# goduino3-v0_22.net
KiCad netlist of a schematic drawn in EAGLE
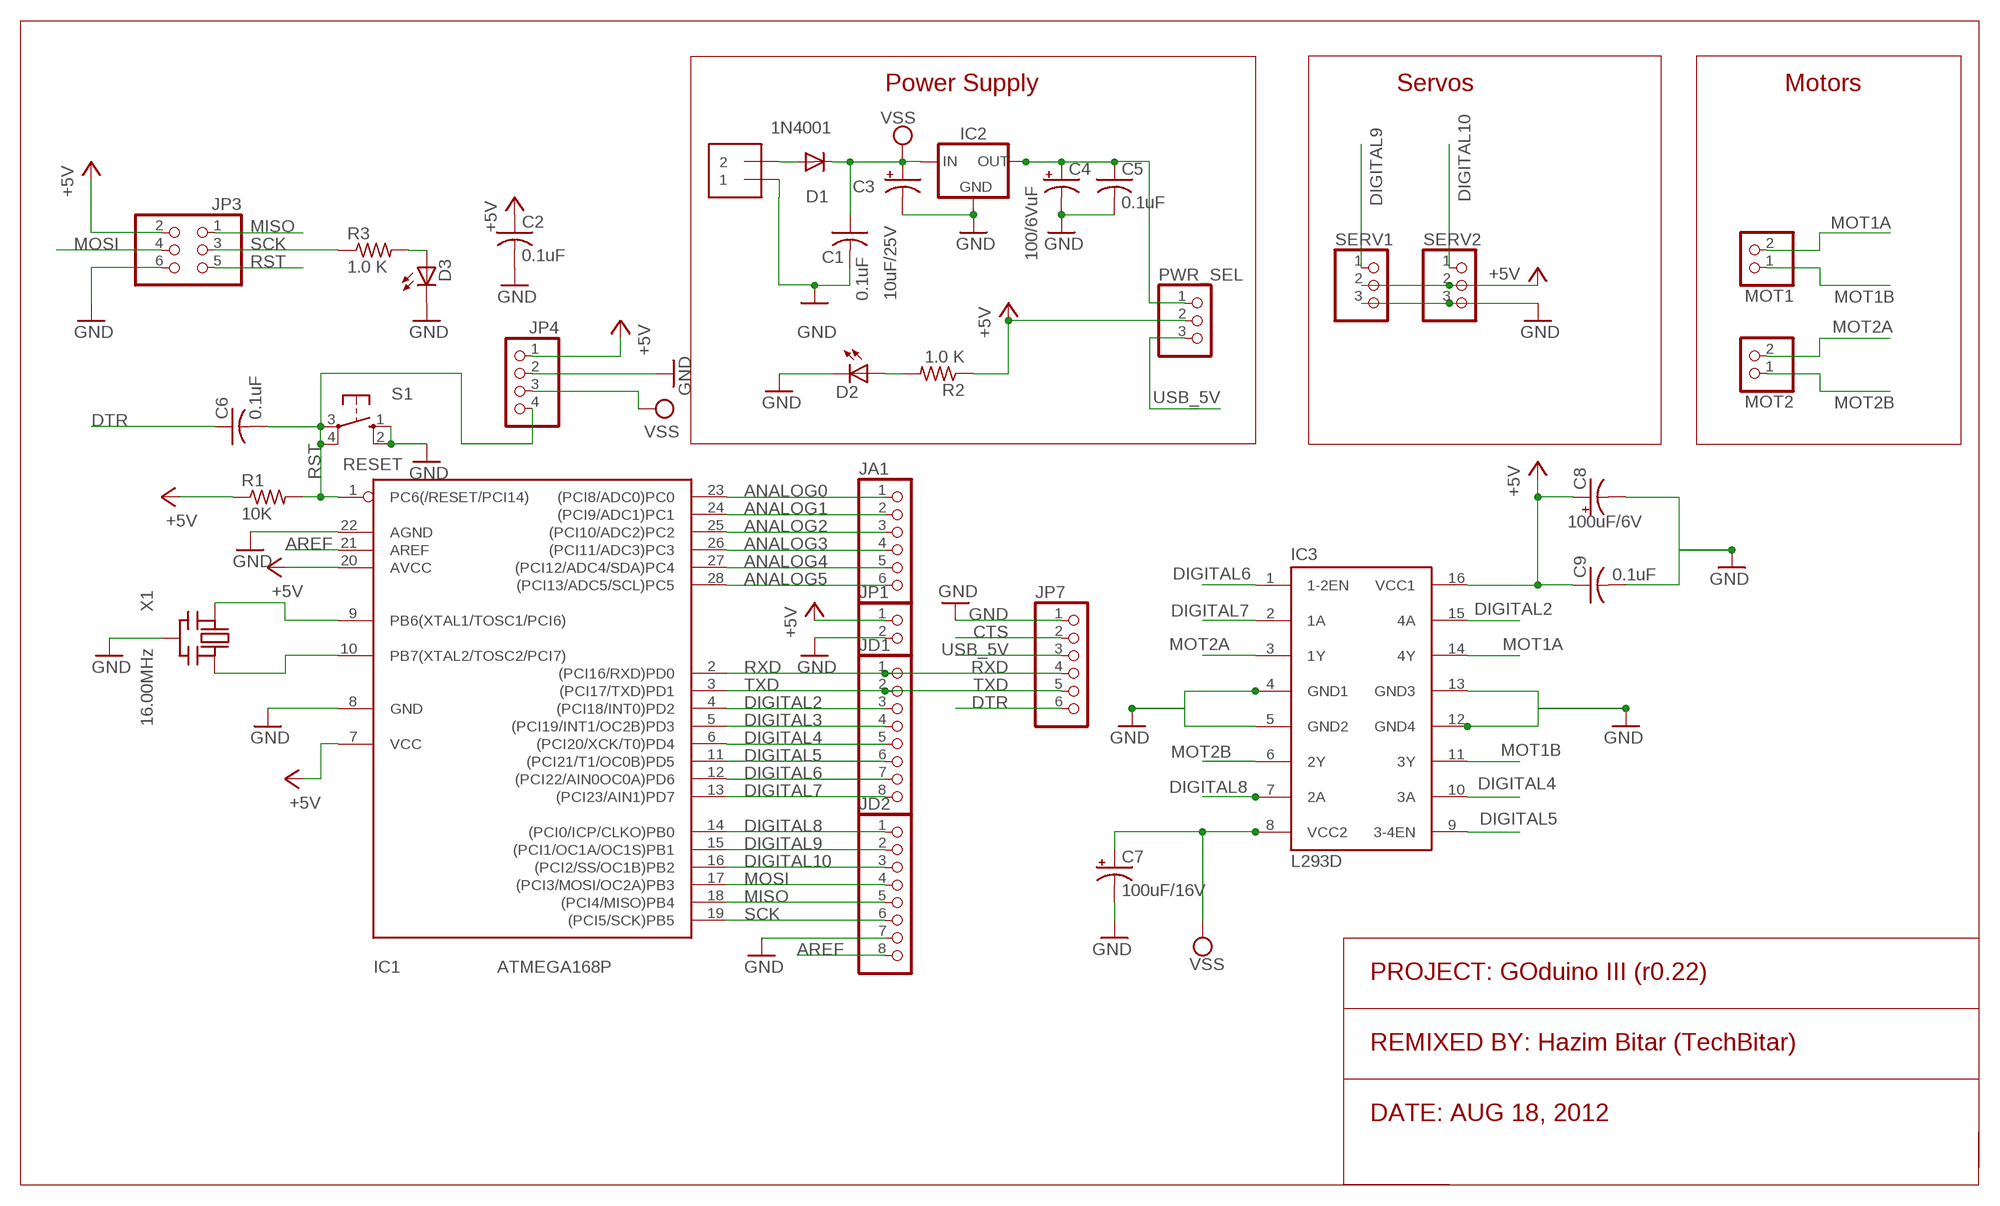
[diagram p0: schematic, sheet 1]

(export (version "E")
  (design (tool "Eeschema 10.0.6"))
  (components
    (comp (ref "C1")
      (value "0.1uF")
      (footprint "eagle-import:C025-025X050")
      (libsource (lib "eagle-import") (part "C-US025-025X050"))
    )
    (comp (ref "C2")
      (value "0.1uF")
      (footprint "eagle-import:C025-025X050")
      (libsource (lib "eagle-import") (part "C-US025-025X050"))
    )
    (comp (ref "C3")
      (value "10uF/25V")
      (footprint "eagle-import:E2,5-6")
      (libsource (lib "eagle-import") (part "CPOL-USE2.5-6"))
    )
    (comp (ref "C4")
      (value "100/6VuF")
      (footprint "eagle-import:E2,5-6")
      (libsource (lib "eagle-import") (part "CPOL-USE2.5-6"))
    )
    (comp (ref "C5")
      (value "0.1uF")
      (footprint "eagle-import:C025-025X050")
      (libsource (lib "eagle-import") (part "C-US025-025X050"))
    )
    (comp (ref "C6")
      (value "0.1uF")
      (footprint "eagle-import:C025-025X050")
      (libsource (lib "eagle-import") (part "C-US025-025X050"))
    )
    (comp (ref "C7")
      (value "100uF/16V")
      (footprint "eagle-import:E2,5-6")
      (libsource (lib "eagle-import") (part "rcl_CPOL-USE2.5-6"))
    )
    (comp (ref "C8")
      (value "100uF/6V")
      (footprint "eagle-import:E2,5-5")
      (libsource (lib "eagle-import") (part "rcl_CPOL-USE2.5-5"))
    )
    (comp (ref "C9")
      (value "0.1uF")
      (footprint "eagle-import:C025-025X050")
      (libsource (lib "eagle-import") (part "rcl_C-US025-025X050"))
    )
    (comp (ref "D1")
      (value "1N4001")
      (footprint "eagle-import:DO41-10")
      (libsource (lib "eagle-import") (part "1N4004"))
    )
    (comp (ref "D2")
      (value "LED3MM")
      (footprint "eagle-import:LED3MM")
      (libsource (lib "eagle-import") (part "LED3MM"))
    )
    (comp (ref "D3")
      (value "Green")
      (footprint "eagle-import:LED3MM")
      (libsource (lib "eagle-import") (part "LED3MM"))
    )
    (comp (ref "IC1")
      (value "ATMEGA168P")
      (footprint "eagle-import:DIL28_3")
      (libsource (lib "eagle-import") (part "ATMEGA168PROUND"))
    )
    (comp (ref "IC2")
      (value "78XXS")
      (footprint "eagle-import:78XXS")
      (libsource (lib "eagle-import") (part "78XXS"))
    )
    (comp (ref "IC3")
      (value "L293D")
      (footprint "eagle-import:DIL16")
      (libsource (lib "eagle-import") (part "L293D"))
    )
    (comp (ref "J2")
      (value "1X2-3.5MM")
      (footprint "eagle-import:1X2-3.5MM")
      (libsource (lib "eagle-import") (part "1X2-3.5MM"))
    )
    (comp (ref "JA1")
      (value "PINHD-1X6CB")
      (footprint "eagle-import:1X06-CLEANBIG")
      (libsource (lib "eagle-import") (part "PINHD-1X6CB"))
    )
    (comp (ref "JD1")
      (value "PINHD-1X8CLEANBIG")
      (footprint "eagle-import:1X08-CLEANBIG")
      (libsource (lib "eagle-import") (part "PINHD-1X8CLEANBIG"))
    )
    (comp (ref "JD2")
      (value "PINHD-1X8CLEANBIG")
      (footprint "eagle-import:1X08-CLEANBIG")
      (libsource (lib "eagle-import") (part "PINHD-1X8CLEANBIG"))
    )
    (comp (ref "JP1")
      (value "PINHD-1X2CB")
      (footprint "eagle-import:1X02-CB")
      (libsource (lib "eagle-import") (part "PINHD-1X2CB"))
    )
    (comp (ref "JP3")
      (value "PINHD-2X3")
      (footprint "eagle-import:2X03")
      (libsource (lib "eagle-import") (part "PINHD-2X3"))
    )
    (comp (ref "JP4")
      (value "PINHD-1X4CB")
      (footprint "eagle-import:1X04-CB")
      (libsource (lib "eagle-import") (part "PINHD-1X4CB"))
    )
    (comp (ref "JP7")
      (value "PINHD-1X6CLEAN")
      (footprint "eagle-import:1X06-CLEAN")
      (libsource (lib "eagle-import") (part "PINHD-1X6CLEAN"))
    )
    (comp (ref "MOT1")
      (value "PINHD-1X2CB")
      (footprint "eagle-import:1X02-CB")
      (libsource (lib "eagle-import") (part "PINHD-1X2CB"))
    )
    (comp (ref "MOT2")
      (value "PINHD-1X2CB")
      (footprint "eagle-import:1X02-CB")
      (libsource (lib "eagle-import") (part "PINHD-1X2CB"))
    )
    (comp (ref "PWR_SEL")
      (value "PINHD-1X3")
      (footprint "eagle-import:1X03")
      (libsource (lib "eagle-import") (part "PINHD-1X3"))
    )
    (comp (ref "R1")
      (value "10K")
      (footprint "eagle-import:0207_5V")
      (libsource (lib "eagle-import") (part "rcl-ez_R-US_0207/5V"))
    )
    (comp (ref "R2")
      (value "1.0 K")
      (footprint "eagle-import:0207_5V")
      (libsource (lib "eagle-import") (part "R-US_0207/5V"))
    )
    (comp (ref "R3")
      (value "1.0 K")
      (footprint "eagle-import:0207_5V")
      (libsource (lib "eagle-import") (part "R-US_0207/5V"))
    )
    (comp (ref "S1")
      (value "RESET")
      (footprint "eagle-import:B3F-10XX")
      (libsource (lib "eagle-import") (part "10-XX"))
    )
    (comp (ref "SERV1")
      (value "PINHD-1X3")
      (footprint "eagle-import:1X03")
      (libsource (lib "eagle-import") (part "PINHD-1X3"))
    )
    (comp (ref "SERV2")
      (value "PINHD-1X3")
      (footprint "eagle-import:1X03")
      (libsource (lib "eagle-import") (part "PINHD-1X3"))
    )
    (comp (ref "X1")
      (value "16.00MHz")
      (footprint "eagle-import:CERM_OSC")
      (libsource (lib "eagle-import") (part "CERMOSCILL"))
    )
  )
  (nets
    (net (code "1") (name "+5V") (class "Default")
      (node (ref "C2") (pin "1") (pinfunction "1_1") (pintype "passive"))
      (node (ref "C8") (pin "+") (pinfunction "+_+") (pintype "passive"))
      (node (ref "C9") (pin "1") (pinfunction "1_1") (pintype "passive"))
      (node (ref "IC1") (pin "20") (pinfunction "AVCC_20") (pintype "bidirectional"))
      (node (ref "IC1") (pin "7") (pinfunction "VCC_7") (pintype "bidirectional"))
      (node (ref "IC3") (pin "16") (pinfunction "VCC1_16") (pintype "power_in"))
      (node (ref "JP1") (pin "1") (pinfunction "1_1") (pintype "passive"))
      (node (ref "JP3") (pin "2") (pinfunction "2_2") (pintype "passive"))
      (node (ref "JP4") (pin "1") (pinfunction "1_1") (pintype "passive"))
      (node (ref "PWR_SEL") (pin "2") (pinfunction "2_2") (pintype "passive"))
      (node (ref "R1") (pin "1") (pinfunction "1_1") (pintype "passive"))
      (node (ref "R2") (pin "1") (pinfunction "1_1") (pintype "passive"))
      (node (ref "SERV1") (pin "2") (pinfunction "2_2") (pintype "passive"))
      (node (ref "SERV2") (pin "2") (pinfunction "2_2") (pintype "passive"))
    )
    (net (code "2") (name "/ANALOG0") (class "Default")
      (node (ref "IC1") (pin "23") (pinfunction "(PCI8/ADC0)PC0_23") (pintype "bidirectional"))
      (node (ref "JA1") (pin "1") (pinfunction "1_1") (pintype "passive"))
    )
    (net (code "3") (name "/ANALOG1") (class "Default")
      (node (ref "IC1") (pin "24") (pinfunction "(PCI9/ADC1)PC1_24") (pintype "bidirectional"))
      (node (ref "JA1") (pin "2") (pinfunction "2_2") (pintype "passive"))
    )
    (net (code "4") (name "/ANALOG2") (class "Default")
      (node (ref "IC1") (pin "25") (pinfunction "(PCI10/ADC2)PC2_25") (pintype "bidirectional"))
      (node (ref "JA1") (pin "3") (pinfunction "3_3") (pintype "passive"))
    )
    (net (code "5") (name "/ANALOG3") (class "Default")
      (node (ref "IC1") (pin "26") (pinfunction "(PCI11/ADC3)PC3_26") (pintype "bidirectional"))
      (node (ref "JA1") (pin "4") (pinfunction "4_4") (pintype "passive"))
    )
    (net (code "6") (name "/ANALOG4") (class "Default")
      (node (ref "IC1") (pin "27") (pinfunction "(PCI12/ADC4/SDA)PC4_27") (pintype "bidirectional"))
      (node (ref "JA1") (pin "5") (pinfunction "5_5") (pintype "passive"))
    )
    (net (code "7") (name "/ANALOG5") (class "Default")
      (node (ref "IC1") (pin "28") (pinfunction "(PCI13/ADC5/SCL)PC5_28") (pintype "bidirectional"))
      (node (ref "JA1") (pin "6") (pinfunction "6_6") (pintype "passive"))
    )
    (net (code "8") (name "/AREF") (class "Default")
      (node (ref "IC1") (pin "21") (pinfunction "AREF_21") (pintype "bidirectional"))
      (node (ref "JD2") (pin "8") (pinfunction "8_8") (pintype "passive"))
    )
    (net (code "9") (name "/CTS") (class "Default")
      (node (ref "JP7") (pin "2") (pinfunction "2_2") (pintype "passive"))
    )
    (net (code "10") (name "/DIGITAL2") (class "Default")
      (node (ref "IC1") (pin "4") (pinfunction "(PCI18/INT0)PD2_4") (pintype "bidirectional"))
      (node (ref "IC3") (pin "15") (pinfunction "4A_15") (pintype "input"))
      (node (ref "JD1") (pin "3") (pinfunction "3_3") (pintype "passive"))
    )
    (net (code "11") (name "/DIGITAL3") (class "Default")
      (node (ref "IC1") (pin "5") (pinfunction "(PCI19/INT1/OC2B)PD3_5") (pintype "bidirectional"))
      (node (ref "JD1") (pin "4") (pinfunction "4_4") (pintype "passive"))
    )
    (net (code "12") (name "/DIGITAL4") (class "Default")
      (node (ref "IC1") (pin "6") (pinfunction "(PCI20/XCK/T0)PD4_6") (pintype "bidirectional"))
      (node (ref "IC3") (pin "10") (pinfunction "3A_10") (pintype "input"))
      (node (ref "JD1") (pin "5") (pinfunction "5_5") (pintype "passive"))
    )
    (net (code "13") (name "/DIGITAL5") (class "Default")
      (node (ref "IC1") (pin "11") (pinfunction "(PCI21/T1/OC0B)PD5_11") (pintype "bidirectional"))
      (node (ref "IC3") (pin "9") (pinfunction "3-4EN_9") (pintype "input"))
      (node (ref "JD1") (pin "6") (pinfunction "6_6") (pintype "passive"))
    )
    (net (code "14") (name "/DIGITAL6") (class "Default")
      (node (ref "IC1") (pin "12") (pinfunction "(PCI22/AIN0OC0A)PD6_12") (pintype "bidirectional"))
      (node (ref "IC3") (pin "1") (pinfunction "1-2EN_1") (pintype "input"))
      (node (ref "JD1") (pin "7") (pinfunction "7_7") (pintype "passive"))
    )
    (net (code "15") (name "/DIGITAL7") (class "Default")
      (node (ref "IC1") (pin "13") (pinfunction "(PCI23/AIN1)PD7_13") (pintype "bidirectional"))
      (node (ref "IC3") (pin "2") (pinfunction "1A_2") (pintype "input"))
      (node (ref "JD1") (pin "8") (pinfunction "8_8") (pintype "passive"))
    )
    (net (code "16") (name "/DIGITAL8") (class "Default")
      (node (ref "IC1") (pin "14") (pinfunction "(PCI0/ICP/CLKO)PB0_14") (pintype "bidirectional"))
      (node (ref "IC3") (pin "7") (pinfunction "2A_7") (pintype "input"))
      (node (ref "JD2") (pin "1") (pinfunction "1_1") (pintype "passive"))
    )
    (net (code "17") (name "/DIGITAL9") (class "Default")
      (node (ref "IC1") (pin "15") (pinfunction "(PCI1/OC1A/OC1S)PB1_15") (pintype "bidirectional"))
      (node (ref "JD2") (pin "2") (pinfunction "2_2") (pintype "passive"))
      (node (ref "SERV1") (pin "1") (pinfunction "1_1") (pintype "passive"))
    )
    (net (code "18") (name "/DIGITAL10") (class "Default")
      (node (ref "IC1") (pin "16") (pinfunction "(PCI2/SS/OC1B)PB2_16") (pintype "bidirectional"))
      (node (ref "JD2") (pin "3") (pinfunction "3_3") (pintype "passive"))
      (node (ref "SERV2") (pin "1") (pinfunction "1_1") (pintype "passive"))
    )
    (net (code "19") (name "/DTR") (class "Default")
      (node (ref "C6") (pin "1") (pinfunction "1_1") (pintype "passive"))
      (node (ref "JP7") (pin "6") (pinfunction "6_6") (pintype "passive"))
    )
    (net (code "20") (name "/MISO") (class "Default")
      (node (ref "IC1") (pin "18") (pinfunction "(PCI4/MISO)PB4_18") (pintype "bidirectional"))
      (node (ref "JD2") (pin "5") (pinfunction "5_5") (pintype "passive"))
      (node (ref "JP3") (pin "1") (pinfunction "1_1") (pintype "passive"))
    )
    (net (code "21") (name "/MOSI") (class "Default")
      (node (ref "IC1") (pin "17") (pinfunction "(PCI3/MOSI/OC2A)PB3_17") (pintype "bidirectional"))
      (node (ref "JD2") (pin "4") (pinfunction "4_4") (pintype "passive"))
      (node (ref "JP3") (pin "4") (pinfunction "4_4") (pintype "passive"))
    )
    (net (code "22") (name "/MOT1A") (class "Default")
      (node (ref "IC3") (pin "14") (pinfunction "4Y_14") (pintype "output"))
      (node (ref "MOT1") (pin "2") (pinfunction "2_2") (pintype "passive"))
    )
    (net (code "23") (name "/MOT1B") (class "Default")
      (node (ref "IC3") (pin "11") (pinfunction "3Y_11") (pintype "output"))
      (node (ref "MOT1") (pin "1") (pinfunction "1_1") (pintype "passive"))
    )
    (net (code "24") (name "/MOT2A") (class "Default")
      (node (ref "IC3") (pin "3") (pinfunction "1Y_3") (pintype "output"))
      (node (ref "MOT2") (pin "2") (pinfunction "2_2") (pintype "passive"))
    )
    (net (code "25") (name "/MOT2B") (class "Default")
      (node (ref "IC3") (pin "6") (pinfunction "2Y_6") (pintype "output"))
      (node (ref "MOT2") (pin "1") (pinfunction "1_1") (pintype "passive"))
    )
    (net (code "26") (name "/RST") (class "Default")
      (node (ref "C6") (pin "2") (pinfunction "2_2") (pintype "passive"))
      (node (ref "IC1") (pin "1") (pinfunction "PC6(/RESET/PCI14)_1") (pintype "bidirectional"))
      (node (ref "JP3") (pin "5") (pinfunction "5_5") (pintype "passive"))
      (node (ref "JP4") (pin "4") (pinfunction "4_4") (pintype "passive"))
      (node (ref "R1") (pin "2") (pinfunction "2_2") (pintype "passive"))
      (node (ref "S1") (pin "3") (pinfunction "P_3") (pintype "passive"))
      (node (ref "S1") (pin "4") (pinfunction "P1_4") (pintype "passive"))
    )
    (net (code "27") (name "/RXD") (class "Default")
      (node (ref "IC1") (pin "2") (pinfunction "(PCI16/RXD)PD0_2") (pintype "bidirectional"))
      (node (ref "JD1") (pin "1") (pinfunction "1_1") (pintype "passive"))
      (node (ref "JP7") (pin "4") (pinfunction "4_4") (pintype "passive"))
    )
    (net (code "28") (name "/SCK") (class "Default")
      (node (ref "IC1") (pin "19") (pinfunction "(PCI5/SCK)PB5_19") (pintype "bidirectional"))
      (node (ref "JD2") (pin "6") (pinfunction "6_6") (pintype "passive"))
      (node (ref "JP3") (pin "3") (pinfunction "3_3") (pintype "passive"))
      (node (ref "R3") (pin "1") (pinfunction "1_1") (pintype "passive"))
    )
    (net (code "29") (name "/TXD") (class "Default")
      (node (ref "IC1") (pin "3") (pinfunction "(PCI17/TXD)PD1_3") (pintype "bidirectional"))
      (node (ref "JD1") (pin "2") (pinfunction "2_2") (pintype "passive"))
      (node (ref "JP7") (pin "5") (pinfunction "5_5") (pintype "passive"))
    )
    (net (code "30") (name "/USB_5V") (class "Default")
      (node (ref "JP7") (pin "3") (pinfunction "3_3") (pintype "passive"))
      (node (ref "PWR_SEL") (pin "3") (pinfunction "3_3") (pintype "passive"))
    )
    (net (code "31") (name "GND") (class "Default")
      (node (ref "C1") (pin "2") (pinfunction "2_2") (pintype "passive"))
      (node (ref "C2") (pin "2") (pinfunction "2_2") (pintype "passive"))
      (node (ref "C3") (pin "-") (pinfunction "-_-") (pintype "passive"))
      (node (ref "C4") (pin "-") (pinfunction "-_-") (pintype "passive"))
      (node (ref "C5") (pin "2") (pinfunction "2_2") (pintype "passive"))
      (node (ref "C7") (pin "-") (pinfunction "-_-") (pintype "passive"))
      (node (ref "C8") (pin "-") (pinfunction "-_-") (pintype "passive"))
      (node (ref "C9") (pin "2") (pinfunction "2_2") (pintype "passive"))
      (node (ref "D2") (pin "K") (pinfunction "C_K") (pintype "passive"))
      (node (ref "D3") (pin "K") (pinfunction "C_K") (pintype "passive"))
      (node (ref "IC1") (pin "22") (pinfunction "AGND_22") (pintype "bidirectional"))
      (node (ref "IC1") (pin "8") (pinfunction "GND_8") (pintype "bidirectional"))
      (node (ref "IC2") (pin "GND") (pinfunction "GND_GND") (pintype "input"))
      (node (ref "IC3") (pin "12") (pinfunction "GND4_12") (pintype "power_in"))
      (node (ref "IC3") (pin "13") (pinfunction "GND3_13") (pintype "power_in"))
      (node (ref "IC3") (pin "4") (pinfunction "GND1_4") (pintype "power_in"))
      (node (ref "IC3") (pin "5") (pinfunction "GND2_5") (pintype "power_in"))
      (node (ref "J2") (pin "1") (pinfunction "1_1") (pintype "passive"))
      (node (ref "JD2") (pin "7") (pinfunction "7_7") (pintype "passive"))
      (node (ref "JP1") (pin "2") (pinfunction "2_2") (pintype "passive"))
      (node (ref "JP3") (pin "6") (pinfunction "6_6") (pintype "passive"))
      (node (ref "JP4") (pin "2") (pinfunction "2_2") (pintype "passive"))
      (node (ref "JP7") (pin "1") (pinfunction "1_1") (pintype "passive"))
      (node (ref "S1") (pin "1") (pinfunction "S_1") (pintype "passive"))
      (node (ref "S1") (pin "2") (pinfunction "S1_2") (pintype "passive"))
      (node (ref "SERV1") (pin "3") (pinfunction "3_3") (pintype "passive"))
      (node (ref "SERV2") (pin "3") (pinfunction "3_3") (pintype "passive"))
      (node (ref "X1") (pin "P$2") (pinfunction "GND_P$2") (pintype "bidirectional"))
    )
    (net (code "32") (name "Net-(C4-Pad+)") (class "Default")
      (node (ref "C4") (pin "+") (pinfunction "+_+") (pintype "passive"))
      (node (ref "C5") (pin "1") (pinfunction "1_1") (pintype "passive"))
      (node (ref "IC2") (pin "OUT") (pinfunction "OUT_OUT") (pintype "passive"))
      (node (ref "PWR_SEL") (pin "1") (pinfunction "1_1") (pintype "passive"))
    )
    (net (code "33") (name "Net-(D2-PadA)") (class "Default")
      (node (ref "D2") (pin "A") (pinfunction "A_A") (pintype "passive"))
      (node (ref "R2") (pin "2") (pinfunction "2_2") (pintype "passive"))
    )
    (net (code "34") (name "Net-(D3-PadA)") (class "Default")
      (node (ref "D3") (pin "A") (pinfunction "A_A") (pintype "passive"))
      (node (ref "R3") (pin "2") (pinfunction "2_2") (pintype "passive"))
    )
    (net (code "35") (name "Net-(IC1-PB6(XTAL1{slash}TOSC1{slash}PCI6))") (class "Default")
      (node (ref "IC1") (pin "9") (pinfunction "PB6(XTAL1/TOSC1/PCI6)_9") (pintype "bidirectional"))
      (node (ref "X1") (pin "P$1") (pinfunction "IN_P$1") (pintype "bidirectional"))
    )
    (net (code "36") (name "Net-(IC1-PB7(XTAL2{slash}TOSC2{slash}PCI7))") (class "Default")
      (node (ref "IC1") (pin "10") (pinfunction "PB7(XTAL2/TOSC2/PCI7)_10") (pintype "bidirectional"))
      (node (ref "X1") (pin "P$3") (pinfunction "OUT_P$3") (pintype "bidirectional"))
    )
    (net (code "37") (name "VSS") (class "Default")
      (node (ref "C1") (pin "1") (pinfunction "1_1") (pintype "passive"))
      (node (ref "C3") (pin "+") (pinfunction "+_+") (pintype "passive"))
      (node (ref "C7") (pin "+") (pinfunction "+_+") (pintype "passive"))
      (node (ref "D1") (pin "A") (pinfunction "A_A") (pintype "passive"))
      (node (ref "D1") (pin "C") (pinfunction "C_C") (pintype "passive"))
      (node (ref "IC2") (pin "IN") (pinfunction "IN_IN") (pintype "input"))
      (node (ref "IC3") (pin "8") (pinfunction "VCC2_8") (pintype "power_in"))
      (node (ref "J2") (pin "2") (pinfunction "2_2") (pintype "passive"))
      (node (ref "JP4") (pin "3") (pinfunction "3_3") (pintype "passive"))
    )
  )
)
